# pcb.net
KiCad netlist of a schematic drawn in EAGLE
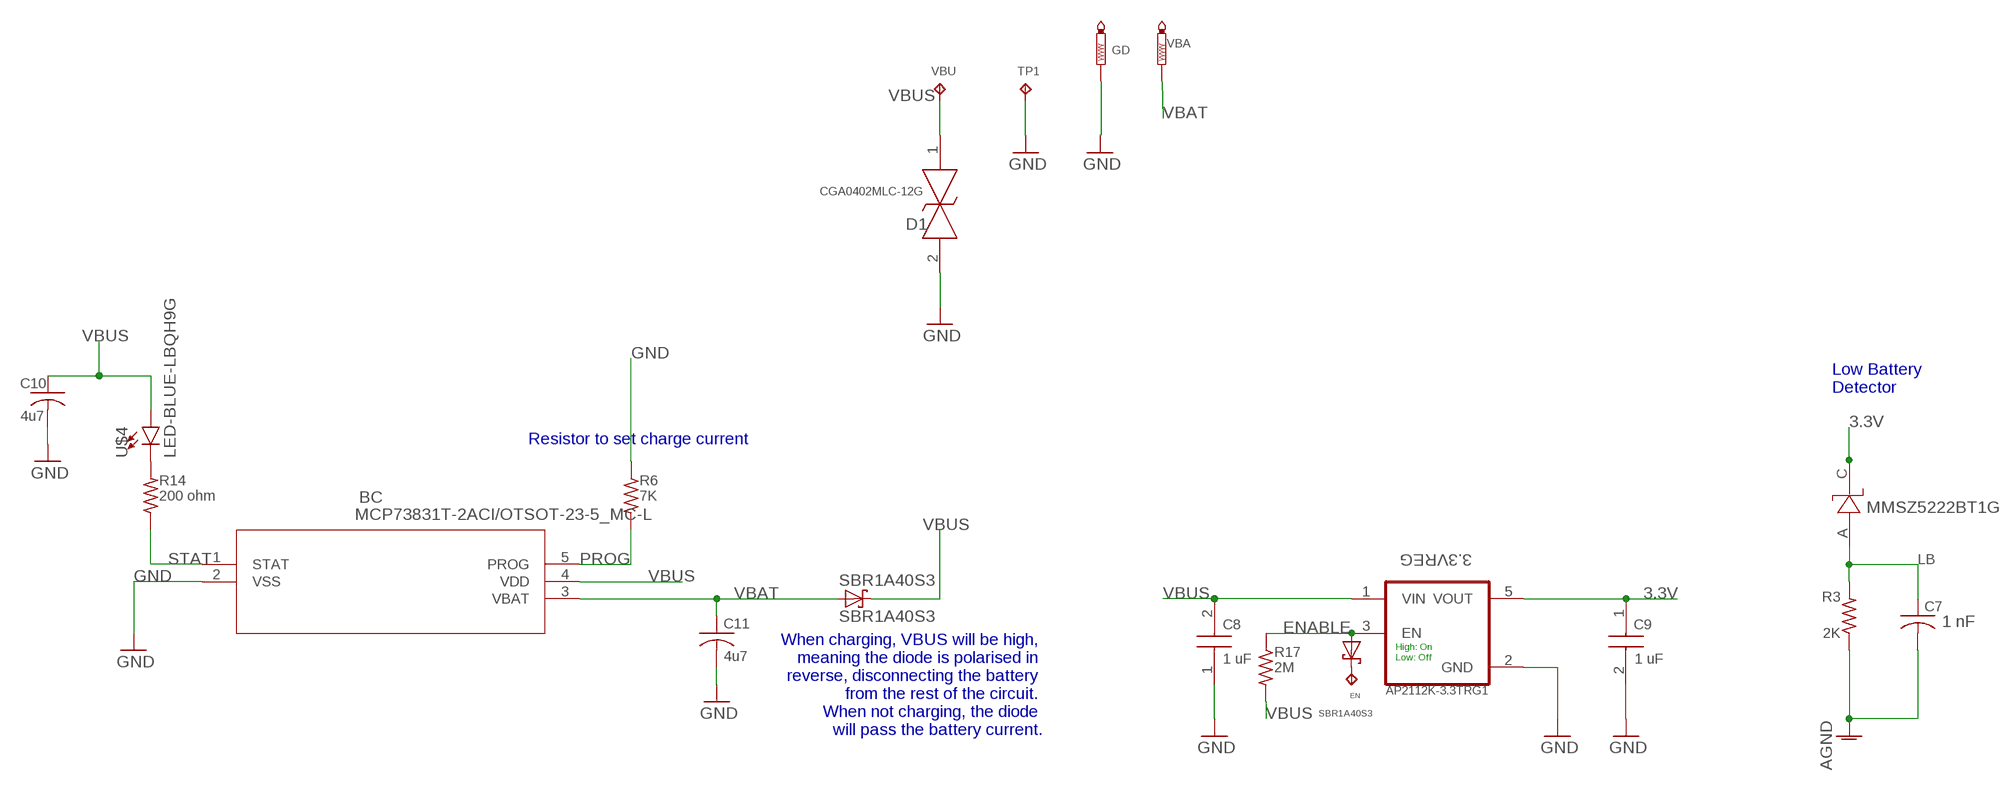
[diagram p0: schematic, sheet 1, part 1 of 2]
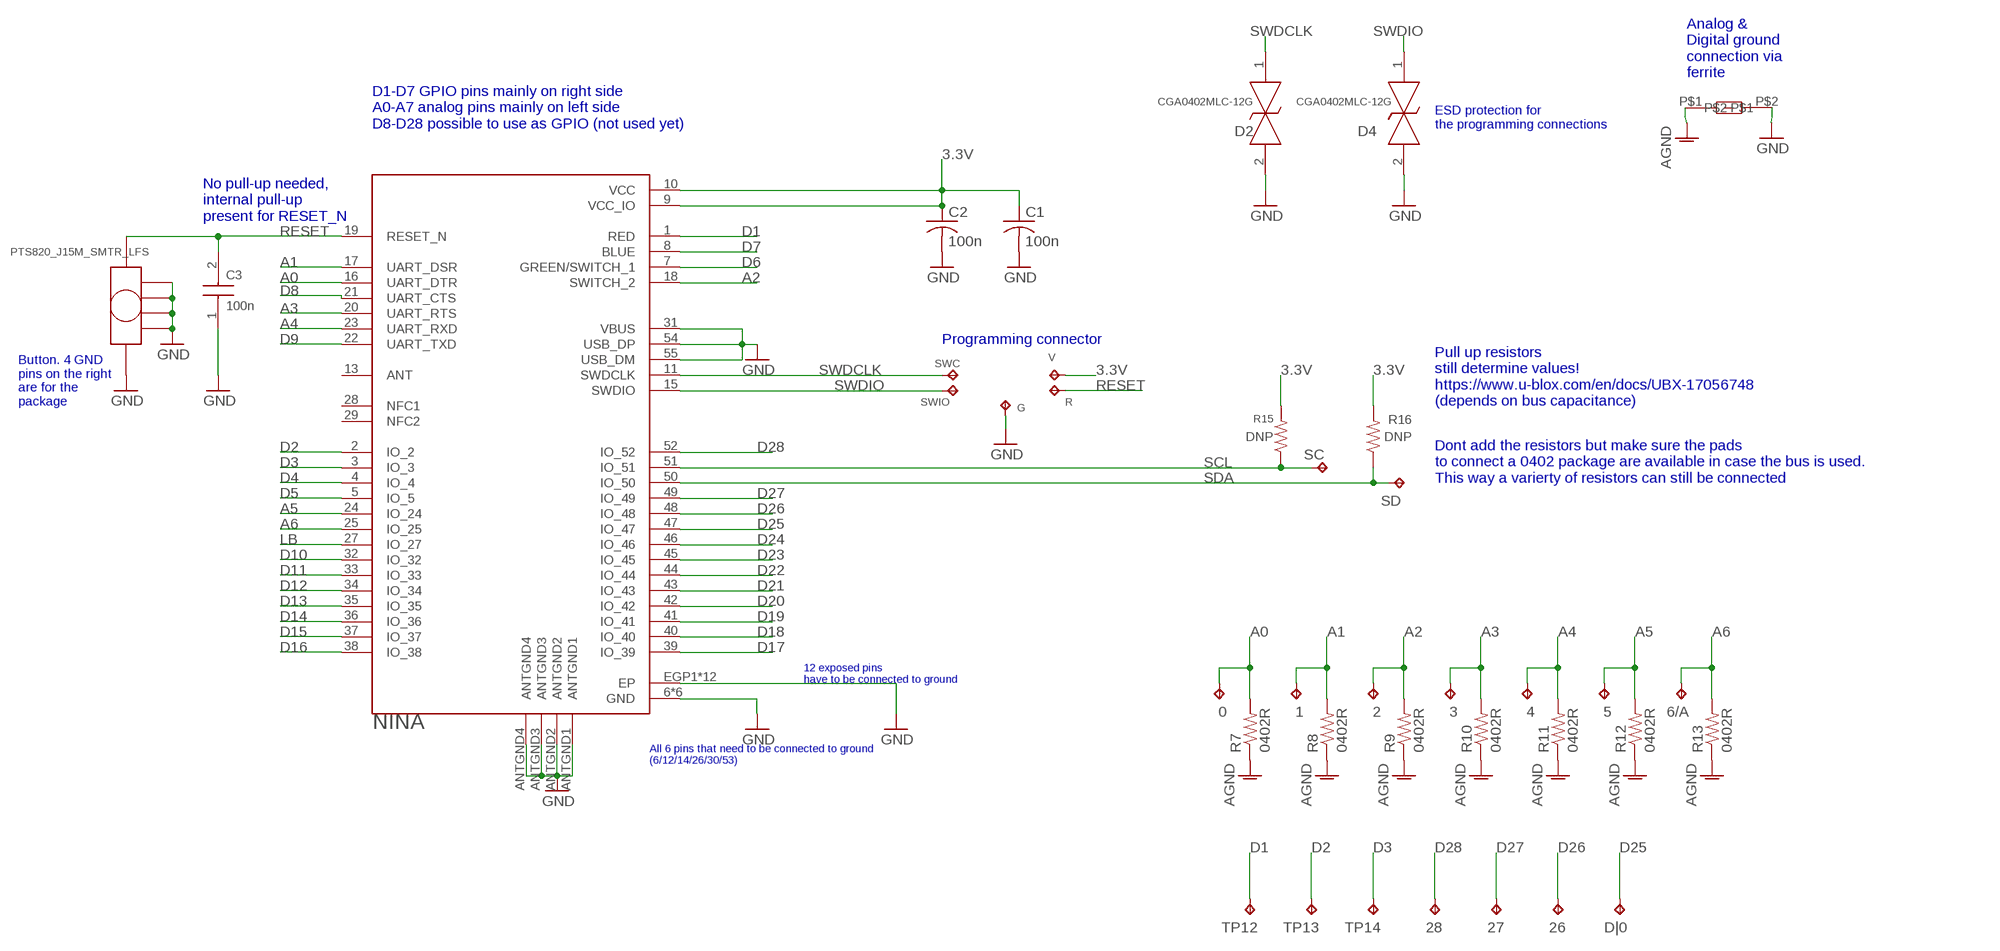
[diagram p1: schematic, sheet 1, part 2 of 2]

(export (version "E")
  (design (tool "Eeschema 10.0.6"))
  (components
    (comp (ref "0")
      (value "CUSTOM_HOLE1")
      (footprint "eagle-import:CUSTOM_HOLE")
      (libsource (lib "eagle-import") (part "CUSTOM_HOLE1"))
    )
    (comp (ref "1")
      (value "CUSTOM_HOLE1")
      (footprint "eagle-import:CUSTOM_HOLE")
      (libsource (lib "eagle-import") (part "CUSTOM_HOLE1"))
    )
    (comp (ref "2")
      (value "CUSTOM_HOLE1")
      (footprint "eagle-import:CUSTOM_HOLE")
      (libsource (lib "eagle-import") (part "CUSTOM_HOLE1"))
    )
    (comp (ref "3")
      (value "CUSTOM_HOLE1")
      (footprint "eagle-import:CUSTOM_HOLE")
      (libsource (lib "eagle-import") (part "CUSTOM_HOLE1"))
    )
    (comp (ref "3.3VREG")
      (value "AP2112K-3.3TRG1")
      (footprint "eagle-import:SOT95P285X140-5N")
      (fields (field (name "MF") "Diodes Inc."))
      (libsource (lib "eagle-import") (part "AP2112K-3.3TRG1"))
    )
    (comp (ref "4")
      (value "CUSTOM_HOLE1")
      (footprint "eagle-import:CUSTOM_HOLE")
      (libsource (lib "eagle-import") (part "CUSTOM_HOLE1"))
    )
    (comp (ref "5")
      (value "CUSTOM_HOLE1")
      (footprint "eagle-import:CUSTOM_HOLE")
      (libsource (lib "eagle-import") (part "CUSTOM_HOLE1"))
    )
    (comp (ref "6/A")
      (value "CUSTOM_HOLE1")
      (footprint "eagle-import:CUSTOM_HOLE")
      (libsource (lib "eagle-import") (part "CUSTOM_HOLE1"))
    )
    (comp (ref "26")
      (value "CUSTOM_HOLE1")
      (footprint "eagle-import:CUSTOM_HOLE")
      (libsource (lib "eagle-import") (part "CUSTOM_HOLE1"))
    )
    (comp (ref "27")
      (value "CUSTOM_HOLE1")
      (footprint "eagle-import:CUSTOM_HOLE")
      (libsource (lib "eagle-import") (part "CUSTOM_HOLE1"))
    )
    (comp (ref "28")
      (value "CUSTOM_HOLE1")
      (footprint "eagle-import:CUSTOM_HOLE")
      (libsource (lib "eagle-import") (part "CUSTOM_HOLE1"))
    )
    (comp (ref "BC")
      (value "MCP73831T-2ACI/OTSOT-23-5_MC-L")
      (footprint "eagle-import:SOT-23-5_MC-L")
      (fields (field (name "MANUFACTURER_PART_NUMBER") "MCP73831T-2ACI/OT"))
      (libsource (lib "eagle-import") (part "MCP73831T-2ACI/OTSOT-23-5_MC-L"))
    )
    (comp (ref "BUTTON")
      (value "PTS820_J15M_SMTR_LFS")
      (footprint "eagle-import:PTS820_J15")
      (fields
        (field (name "MANUFACTURER_PART_NUMBER") "PTS820 J15M SMTR LFS")
        (field (name "MOUSER_PART_NUMBER") "611-PTS820J15MSMTR")
        (field (name "RS_PART_NUMBER") "1359503P")
      )
      (libsource (lib "eagle-import") (part "PTS820_J15M_SMTR_LFS"))
    )
    (comp (ref "C1")
      (value "100n")
      (footprint "eagle-import:C0402")
      (libsource (lib "eagle-import") (part "C-USC0402"))
    )
    (comp (ref "C2")
      (value "100n")
      (footprint "eagle-import:C0402")
      (libsource (lib "eagle-import") (part "C-USC0402"))
    )
    (comp (ref "C3")
      (value "100n")
      (footprint "eagle-import:CAPC1005X33N")
      (fields
        (field (name "MANUFACTURER_PART_NUMBER") "JMK105BJ105KP-F")
        (field (name "MOUSER_PART_NUMBER") "963-JMK105BJ105KP-F")
      )
      (libsource (lib "eagle-import") (part "JMK105BJ105KP-F"))
    )
    (comp (ref "C7")
      (value "1 nF")
      (footprint "eagle-import:C0402")
      (libsource (lib "eagle-import") (part "C-USC0402"))
    )
    (comp (ref "C8")
      (value "1 uF")
      (footprint "eagle-import:CAPC1005X33N")
      (fields
        (field (name "MANUFACTURER_PART_NUMBER") "JMK105BJ105KP-F")
        (field (name "MOUSER_PART_NUMBER") "963-JMK105BJ105KP-F")
      )
      (libsource (lib "eagle-import") (part "JMK105BJ105KP-F"))
    )
    (comp (ref "C9")
      (value "1 uF")
      (footprint "eagle-import:CAPC1005X33N")
      (fields
        (field (name "MANUFACTURER_PART_NUMBER") "JMK105BJ105KP-F")
        (field (name "MOUSER_PART_NUMBER") "963-JMK105BJ105KP-F")
      )
      (libsource (lib "eagle-import") (part "JMK105BJ105KP-F"))
    )
    (comp (ref "C10")
      (value "4u7")
      (footprint "eagle-import:C0402")
      (libsource (lib "eagle-import") (part "C-USC0402"))
    )
    (comp (ref "C11")
      (value "4u7")
      (footprint "eagle-import:C0402")
      (libsource (lib "eagle-import") (part "C-USC0402"))
    )
    (comp (ref "D1")
      (value "CGA0402MLC-12G")
      (footprint "eagle-import:CGA0402MLC12G")
      (fields (field (name "MOUSER_PART_NUMBER") "652-CGA0402MLC-12G"))
      (libsource (lib "eagle-import") (part "CGA0402MLC-12G"))
    )
    (comp (ref "D2")
      (value "CGA0402MLC-12G")
      (footprint "eagle-import:CGA0402MLC12G")
      (fields (field (name "MOUSER_PART_NUMBER") "652-CGA0402MLC-12G"))
      (libsource (lib "eagle-import") (part "CGA0402MLC-12G"))
    )
    (comp (ref "D4")
      (value "CGA0402MLC-12G")
      (footprint "eagle-import:CGA0402MLC12G")
      (fields (field (name "MOUSER_PART_NUMBER") "652-CGA0402MLC-12G"))
      (libsource (lib "eagle-import") (part "CGA0402MLC-12G"))
    )
    (comp (ref "D|0")
      (value "CUSTOM_HOLE1")
      (footprint "eagle-import:CUSTOM_HOLE")
      (libsource (lib "eagle-import") (part "CUSTOM_HOLE1"))
    )
    (comp (ref "EN")
      (value "CUSTOM_HOLE1")
      (footprint "eagle-import:CUSTOM_HOLE")
      (libsource (lib "eagle-import") (part "CUSTOM_HOLE1"))
    )
    (comp (ref "G")
      (value "TPB1,27")
      (footprint "eagle-import:B1,27")
      (libsource (lib "eagle-import") (part "TPB1,27"))
    )
    (comp (ref "GD")
      (value "PTR1TP18R")
      (footprint "eagle-import:TP18R")
      (libsource (lib "eagle-import") (part "PTR1TP18R"))
    )
    (comp (ref "MMSZ5222BT1G")
      (value "MMSZ5222BT1G")
      (footprint "eagle-import:SOD−123")
      (libsource (lib "eagle-import") (part "MMSZ5222BT1G"))
    )
    (comp (ref "R")
      (value "TPB1,27")
      (footprint "eagle-import:B1,27")
      (libsource (lib "eagle-import") (part "TPB1,27"))
    )
    (comp (ref "R3")
      (value "2K")
      (footprint "eagle-import:RESC1005X40N")
      (libsource (lib "eagle-import") (part "0402R"))
    )
    (comp (ref "R6")
      (value "7K")
      (footprint "eagle-import:RESC1005X40N")
      (libsource (lib "eagle-import") (part "0402R"))
    )
    (comp (ref "R7")
      (value "0402R")
      (footprint "eagle-import:RESC1005X40N")
      (libsource (lib "eagle-import") (part "0402R"))
    )
    (comp (ref "R8")
      (value "0402R")
      (footprint "eagle-import:RESC1005X40N")
      (libsource (lib "eagle-import") (part "0402R"))
    )
    (comp (ref "R9")
      (value "0402R")
      (footprint "eagle-import:RESC1005X40N")
      (libsource (lib "eagle-import") (part "0402R"))
    )
    (comp (ref "R10")
      (value "0402R")
      (footprint "eagle-import:RESC1005X40N")
      (libsource (lib "eagle-import") (part "0402R"))
    )
    (comp (ref "R11")
      (value "0402R")
      (footprint "eagle-import:RESC1005X40N")
      (libsource (lib "eagle-import") (part "0402R"))
    )
    (comp (ref "R12")
      (value "0402R")
      (footprint "eagle-import:RESC1005X40N")
      (libsource (lib "eagle-import") (part "0402R"))
    )
    (comp (ref "R13")
      (value "0402R")
      (footprint "eagle-import:RESC1005X40N")
      (libsource (lib "eagle-import") (part "0402R"))
    )
    (comp (ref "R14")
      (value "200 ohm")
      (footprint "eagle-import:RESC1005X40N")
      (libsource (lib "eagle-import") (part "0402R"))
    )
    (comp (ref "R15")
      (value "DNP")
      (footprint "eagle-import:RESC1005X40N")
      (libsource (lib "eagle-import") (part "0402R"))
    )
    (comp (ref "R16")
      (value "DNP")
      (footprint "eagle-import:RESC1005X40N")
      (libsource (lib "eagle-import") (part "0402R"))
    )
    (comp (ref "R17")
      (value "2M")
      (footprint "eagle-import:RESC1005X40N")
      (libsource (lib "eagle-import") (part "0402R"))
    )
    (comp (ref "SBR1A40S3")
      (value "SBR1A40S3")
      (footprint "eagle-import:SOD323")
      (libsource (lib "eagle-import") (part "SBR1A40S3"))
    )
    (comp (ref "SC")
      (value "CUSTOM_HOLE1")
      (footprint "eagle-import:CUSTOM_HOLE")
      (libsource (lib "eagle-import") (part "CUSTOM_HOLE1"))
    )
    (comp (ref "SD")
      (value "CUSTOM_HOLE1")
      (footprint "eagle-import:CUSTOM_HOLE")
      (libsource (lib "eagle-import") (part "CUSTOM_HOLE1"))
    )
    (comp (ref "SWC")
      (value "TPB1,27")
      (footprint "eagle-import:B1,27")
      (libsource (lib "eagle-import") (part "TPB1,27"))
    )
    (comp (ref "SWIO")
      (value "TPB1,27")
      (footprint "eagle-import:B1,27")
      (libsource (lib "eagle-import") (part "TPB1,27"))
    )
    (comp (ref "TP1")
      (value "CUSTOM_HOLE1")
      (footprint "eagle-import:CUSTOM_HOLE")
      (libsource (lib "eagle-import") (part "CUSTOM_HOLE1"))
    )
    (comp (ref "TP12")
      (value "CUSTOM_HOLE1")
      (footprint "eagle-import:CUSTOM_HOLE")
      (libsource (lib "eagle-import") (part "CUSTOM_HOLE1"))
    )
    (comp (ref "TP13")
      (value "CUSTOM_HOLE1")
      (footprint "eagle-import:CUSTOM_HOLE")
      (libsource (lib "eagle-import") (part "CUSTOM_HOLE1"))
    )
    (comp (ref "TP14")
      (value "CUSTOM_HOLE1")
      (footprint "eagle-import:CUSTOM_HOLE")
      (libsource (lib "eagle-import") (part "CUSTOM_HOLE1"))
    )
    (comp (ref "U$2")
      (value "SBR1A40S3")
      (footprint "eagle-import:SOD323")
      (libsource (lib "eagle-import") (part "SBR1A40S3"))
    )
    (comp (ref "U$4")
      (value "LED-BLUE-LBQH9G")
      (footprint "eagle-import:LBQH9G-0402")
      (libsource (lib "eagle-import") (part "LED-BLUE-LBQH9G"))
    )
    (comp (ref "U$5")
      (value "BLM18KG121WH1D")
      (footprint "eagle-import:0603")
      (libsource (lib "eagle-import") (part "BLM18KG121WH1D"))
    )
    (comp (ref "U1")
      (value "NINA")
      (footprint "eagle-import:XCVR_NINA-B306")
      (fields (field (name "MF") "U-Blox America Inc.") (field (name "MP") "NINA-B311-00B"))
      (libsource (lib "eagle-import") (part "NINA-B306"))
    )
    (comp (ref "V")
      (value "TPB1,27")
      (footprint "eagle-import:B1,27")
      (libsource (lib "eagle-import") (part "TPB1,27"))
    )
    (comp (ref "VBA")
      (value "PTR1TP18R")
      (footprint "eagle-import:TP18R")
      (libsource (lib "eagle-import") (part "PTR1TP18R"))
    )
    (comp (ref "VBU")
      (value "CUSTOM_HOLE1")
      (footprint "eagle-import:CUSTOM_HOLE")
      (libsource (lib "eagle-import") (part "CUSTOM_HOLE1"))
    )
  )
  (nets
    (net (code "1") (name "/3.3V") (class "Default")
      (node (ref "3.3VREG") (pin "5") (pinfunction "VOUT_5") (pintype "power_in"))
      (node (ref "C1") (pin "1") (pinfunction "1_1") (pintype "passive"))
      (node (ref "C2") (pin "1") (pinfunction "1_1") (pintype "passive"))
      (node (ref "C9") (pin "1") (pinfunction "1_1") (pintype "bidirectional"))
      (node (ref "MMSZ5222BT1G") (pin "C") (pinfunction "C_C") (pintype "bidirectional"))
      (node (ref "R15") (pin "2") (pinfunction "2_2") (pintype "passive"))
      (node (ref "R16") (pin "2") (pinfunction "2_2") (pintype "passive"))
      (node (ref "U1") (pin "10") (pinfunction "VCC_10") (pintype "power_in"))
      (node (ref "U1") (pin "9") (pinfunction "VCC_IO_9") (pintype "power_in"))
      (node (ref "V") (pin "TP") (pinfunction "TP_TP") (pintype "input"))
    )
    (net (code "2") (name "/A0") (class "Default")
      (node (ref "0") (pin "P$1") (pinfunction "TP_P$1") (pintype "input"))
      (node (ref "R7") (pin "2") (pinfunction "2_2") (pintype "passive"))
      (node (ref "U1") (pin "16") (pinfunction "UART_DTR_16") (pintype "output"))
    )
    (net (code "3") (name "/A1") (class "Default")
      (node (ref "1") (pin "P$1") (pinfunction "TP_P$1") (pintype "input"))
      (node (ref "R8") (pin "2") (pinfunction "2_2") (pintype "passive"))
      (node (ref "U1") (pin "17") (pinfunction "UART_DSR_17") (pintype "input"))
    )
    (net (code "4") (name "/A2") (class "Default")
      (node (ref "2") (pin "P$1") (pinfunction "TP_P$1") (pintype "input"))
      (node (ref "R9") (pin "2") (pinfunction "2_2") (pintype "passive"))
      (node (ref "U1") (pin "18") (pinfunction "SWITCH_2_18") (pintype "input"))
    )
    (net (code "5") (name "/A3") (class "Default")
      (node (ref "3") (pin "P$1") (pinfunction "TP_P$1") (pintype "input"))
      (node (ref "R10") (pin "2") (pinfunction "2_2") (pintype "passive"))
      (node (ref "U1") (pin "20") (pinfunction "UART_RTS_20") (pintype "output"))
    )
    (net (code "6") (name "/A4") (class "Default")
      (node (ref "4") (pin "P$1") (pinfunction "TP_P$1") (pintype "input"))
      (node (ref "R11") (pin "2") (pinfunction "2_2") (pintype "passive"))
      (node (ref "U1") (pin "23") (pinfunction "UART_RXD_23") (pintype "input"))
    )
    (net (code "7") (name "/A5") (class "Default")
      (node (ref "5") (pin "P$1") (pinfunction "TP_P$1") (pintype "input"))
      (node (ref "R12") (pin "2") (pinfunction "2_2") (pintype "passive"))
      (node (ref "U1") (pin "24") (pinfunction "IO_24_24") (pintype "bidirectional"))
    )
    (net (code "8") (name "/A6") (class "Default")
      (node (ref "6/A") (pin "P$1") (pinfunction "TP_P$1") (pintype "input"))
      (node (ref "R13") (pin "2") (pinfunction "2_2") (pintype "passive"))
      (node (ref "U1") (pin "25") (pinfunction "IO_25_25") (pintype "bidirectional"))
    )
    (net (code "9") (name "/D1") (class "Default")
      (node (ref "TP12") (pin "P$1") (pinfunction "TP_P$1") (pintype "input"))
      (node (ref "U1") (pin "1") (pinfunction "RED_1") (pintype "output"))
    )
    (net (code "10") (name "/D2") (class "Default")
      (node (ref "TP13") (pin "P$1") (pinfunction "TP_P$1") (pintype "input"))
      (node (ref "U1") (pin "2") (pinfunction "IO_2_2") (pintype "bidirectional"))
    )
    (net (code "11") (name "/D3") (class "Default")
      (node (ref "TP14") (pin "P$1") (pinfunction "TP_P$1") (pintype "input"))
      (node (ref "U1") (pin "3") (pinfunction "IO_3_3") (pintype "bidirectional"))
    )
    (net (code "12") (name "/D4") (class "Default")
      (node (ref "U1") (pin "4") (pinfunction "IO_4_4") (pintype "bidirectional"))
    )
    (net (code "13") (name "/D5") (class "Default")
      (node (ref "U1") (pin "5") (pinfunction "IO_5_5") (pintype "bidirectional"))
    )
    (net (code "14") (name "/D6") (class "Default")
      (node (ref "U1") (pin "7") (pinfunction "GREEN/SWITCH_1_7") (pintype "bidirectional"))
    )
    (net (code "15") (name "/D7") (class "Default")
      (node (ref "U1") (pin "8") (pinfunction "BLUE_8") (pintype "output"))
    )
    (net (code "16") (name "/D8") (class "Default")
      (node (ref "U1") (pin "21") (pinfunction "UART_CTS_21") (pintype "input"))
    )
    (net (code "17") (name "/D9") (class "Default")
      (node (ref "U1") (pin "22") (pinfunction "UART_TXD_22") (pintype "output"))
    )
    (net (code "18") (name "/D10") (class "Default")
      (node (ref "U1") (pin "32") (pinfunction "IO_32_32") (pintype "bidirectional"))
    )
    (net (code "19") (name "/D11") (class "Default")
      (node (ref "U1") (pin "33") (pinfunction "IO_33_33") (pintype "bidirectional"))
    )
    (net (code "20") (name "/D12") (class "Default")
      (node (ref "U1") (pin "34") (pinfunction "IO_34_34") (pintype "bidirectional"))
    )
    (net (code "21") (name "/D13") (class "Default")
      (node (ref "U1") (pin "35") (pinfunction "IO_35_35") (pintype "bidirectional"))
    )
    (net (code "22") (name "/D14") (class "Default")
      (node (ref "U1") (pin "36") (pinfunction "IO_36_36") (pintype "bidirectional"))
    )
    (net (code "23") (name "/D15") (class "Default")
      (node (ref "U1") (pin "37") (pinfunction "IO_37_37") (pintype "bidirectional"))
    )
    (net (code "24") (name "/D16") (class "Default")
      (node (ref "U1") (pin "38") (pinfunction "IO_38_38") (pintype "bidirectional"))
    )
    (net (code "25") (name "/D17") (class "Default")
      (node (ref "U1") (pin "39") (pinfunction "IO_39_39") (pintype "bidirectional"))
    )
    (net (code "26") (name "/D18") (class "Default")
      (node (ref "U1") (pin "40") (pinfunction "IO_40_40") (pintype "bidirectional"))
    )
    (net (code "27") (name "/D19") (class "Default")
      (node (ref "U1") (pin "41") (pinfunction "IO_41_41") (pintype "bidirectional"))
    )
    (net (code "28") (name "/D20") (class "Default")
      (node (ref "U1") (pin "42") (pinfunction "IO_42_42") (pintype "bidirectional"))
    )
    (net (code "29") (name "/D21") (class "Default")
      (node (ref "U1") (pin "43") (pinfunction "IO_43_43") (pintype "bidirectional"))
    )
    (net (code "30") (name "/D22") (class "Default")
      (node (ref "U1") (pin "44") (pinfunction "IO_44_44") (pintype "bidirectional"))
    )
    (net (code "31") (name "/D23") (class "Default")
      (node (ref "U1") (pin "45") (pinfunction "IO_45_45") (pintype "bidirectional"))
    )
    (net (code "32") (name "/D24") (class "Default")
      (node (ref "U1") (pin "46") (pinfunction "IO_46_46") (pintype "bidirectional"))
    )
    (net (code "33") (name "/D25") (class "Default")
      (node (ref "D|0") (pin "P$1") (pinfunction "TP_P$1") (pintype "input"))
      (node (ref "U1") (pin "47") (pinfunction "IO_47_47") (pintype "bidirectional"))
    )
    (net (code "34") (name "/D26") (class "Default")
      (node (ref "26") (pin "P$1") (pinfunction "TP_P$1") (pintype "input"))
      (node (ref "U1") (pin "48") (pinfunction "IO_48_48") (pintype "bidirectional"))
    )
    (net (code "35") (name "/D27") (class "Default")
      (node (ref "27") (pin "P$1") (pinfunction "TP_P$1") (pintype "input"))
      (node (ref "U1") (pin "49") (pinfunction "IO_49_49") (pintype "bidirectional"))
    )
    (net (code "36") (name "/D28") (class "Default")
      (node (ref "28") (pin "P$1") (pinfunction "TP_P$1") (pintype "input"))
      (node (ref "U1") (pin "52") (pinfunction "IO_52_52") (pintype "bidirectional"))
    )
    (net (code "37") (name "/ENABLE") (class "Default")
      (node (ref "3.3VREG") (pin "3") (pinfunction "EN_3") (pintype "input"))
      (node (ref "R17") (pin "1") (pinfunction "1_1") (pintype "passive"))
      (node (ref "U$2") (pin "A") (pinfunction "A_A") (pintype "passive"))
    )
    (net (code "38") (name "/LB") (class "Default")
      (node (ref "C7") (pin "1") (pinfunction "1_1") (pintype "passive"))
      (node (ref "MMSZ5222BT1G") (pin "A") (pinfunction "A_A") (pintype "bidirectional"))
      (node (ref "R3") (pin "2") (pinfunction "2_2") (pintype "passive"))
      (node (ref "U1") (pin "27") (pinfunction "IO_27_27") (pintype "bidirectional"))
    )
    (net (code "39") (name "/PROG") (class "Default")
      (node (ref "BC") (pin "5") (pinfunction "PROG_5") (pintype "passive"))
      (node (ref "R6") (pin "2") (pinfunction "2_2") (pintype "passive"))
    )
    (net (code "40") (name "/RESET") (class "Default")
      (node (ref "BUTTON") (pin "2") (pinfunction "2_2") (pintype "bidirectional"))
      (node (ref "C3") (pin "2") (pinfunction "2_2") (pintype "bidirectional"))
      (node (ref "R") (pin "TP") (pinfunction "TP_TP") (pintype "input"))
      (node (ref "U1") (pin "19") (pinfunction "RESET_N_19") (pintype "input"))
    )
    (net (code "41") (name "/SCL") (class "Default")
      (node (ref "R15") (pin "1") (pinfunction "1_1") (pintype "passive"))
      (node (ref "SC") (pin "P$1") (pinfunction "TP_P$1") (pintype "input"))
      (node (ref "U1") (pin "51") (pinfunction "IO_51_51") (pintype "bidirectional"))
    )
    (net (code "42") (name "/SDA") (class "Default")
      (node (ref "R16") (pin "1") (pinfunction "1_1") (pintype "passive"))
      (node (ref "SD") (pin "P$1") (pinfunction "TP_P$1") (pintype "input"))
      (node (ref "U1") (pin "50") (pinfunction "IO_50_50") (pintype "bidirectional"))
    )
    (net (code "43") (name "/STAT") (class "Default")
      (node (ref "BC") (pin "1") (pinfunction "STAT_1") (pintype "passive"))
      (node (ref "R14") (pin "1") (pinfunction "1_1") (pintype "passive"))
    )
    (net (code "44") (name "/SWDCLK") (class "Default")
      (node (ref "D2") (pin "1") (pinfunction "1_1") (pintype "bidirectional"))
      (node (ref "SWC") (pin "TP") (pinfunction "TP_TP") (pintype "input"))
      (node (ref "U1") (pin "11") (pinfunction "SWDCLK_11") (pintype "bidirectional"))
    )
    (net (code "45") (name "/SWDIO") (class "Default")
      (node (ref "D4") (pin "1") (pinfunction "1_1") (pintype "bidirectional"))
      (node (ref "SWIO") (pin "TP") (pinfunction "TP_TP") (pintype "input"))
      (node (ref "U1") (pin "15") (pinfunction "SWDIO_15") (pintype "bidirectional"))
    )
    (net (code "46") (name "/VBAT") (class "Default")
      (node (ref "BC") (pin "3") (pinfunction "VBAT_3") (pintype "passive"))
      (node (ref "C11") (pin "1") (pinfunction "1_1") (pintype "passive"))
      (node (ref "SBR1A40S3") (pin "A") (pinfunction "A_A") (pintype "passive"))
      (node (ref "VBA") (pin "TP") (pinfunction "TP_TP") (pintype "input"))
    )
    (net (code "47") (name "/VBUS") (class "Default")
      (node (ref "3.3VREG") (pin "1") (pinfunction "VIN_1") (pintype "power_in"))
      (node (ref "BC") (pin "4") (pinfunction "VDD_4") (pintype "passive"))
      (node (ref "C10") (pin "1") (pinfunction "1_1") (pintype "passive"))
      (node (ref "C8") (pin "2") (pinfunction "2_2") (pintype "bidirectional"))
      (node (ref "D1") (pin "1") (pinfunction "1_1") (pintype "bidirectional"))
      (node (ref "R17") (pin "2") (pinfunction "2_2") (pintype "passive"))
      (node (ref "SBR1A40S3") (pin "C") (pinfunction "C_C") (pintype "passive"))
      (node (ref "U$4") (pin "A") (pinfunction "A_A") (pintype "passive"))
      (node (ref "VBU") (pin "P$1") (pinfunction "TP_P$1") (pintype "input"))
    )
    (net (code "48") (name "AGND") (class "Default")
      (node (ref "C7") (pin "2") (pinfunction "2_2") (pintype "passive"))
      (node (ref "R10") (pin "1") (pinfunction "1_1") (pintype "passive"))
      (node (ref "R11") (pin "1") (pinfunction "1_1") (pintype "passive"))
      (node (ref "R12") (pin "1") (pinfunction "1_1") (pintype "passive"))
      (node (ref "R13") (pin "1") (pinfunction "1_1") (pintype "passive"))
      (node (ref "R3") (pin "1") (pinfunction "1_1") (pintype "passive"))
      (node (ref "R7") (pin "1") (pinfunction "1_1") (pintype "passive"))
      (node (ref "R8") (pin "1") (pinfunction "1_1") (pintype "passive"))
      (node (ref "R9") (pin "1") (pinfunction "1_1") (pintype "passive"))
      (node (ref "U$5") (pin "P$1") (pinfunction "P$1_P$1") (pintype "bidirectional"))
    )
    (net (code "49") (name "GND") (class "Default")
      (node (ref "3.3VREG") (pin "2") (pinfunction "GND_2") (pintype "power_in"))
      (node (ref "BC") (pin "2") (pinfunction "VSS_2") (pintype "passive"))
      (node (ref "BUTTON") (pin "1") (pinfunction "1_1") (pintype "bidirectional"))
      (node (ref "BUTTON") (pin "P$1") (pinfunction "P$1_P$1") (pintype "bidirectional"))
      (node (ref "BUTTON") (pin "P$2") (pinfunction "P$2_P$2") (pintype "bidirectional"))
      (node (ref "BUTTON") (pin "P$3") (pinfunction "P$3_P$3") (pintype "bidirectional"))
      (node (ref "BUTTON") (pin "P$4") (pinfunction "P$4_P$4") (pintype "bidirectional"))
      (node (ref "C1") (pin "2") (pinfunction "2_2") (pintype "passive"))
      (node (ref "C10") (pin "2") (pinfunction "2_2") (pintype "passive"))
      (node (ref "C11") (pin "2") (pinfunction "2_2") (pintype "passive"))
      (node (ref "C2") (pin "2") (pinfunction "2_2") (pintype "passive"))
      (node (ref "C3") (pin "1") (pinfunction "1_1") (pintype "bidirectional"))
      (node (ref "C8") (pin "1") (pinfunction "1_1") (pintype "bidirectional"))
      (node (ref "C9") (pin "2") (pinfunction "2_2") (pintype "bidirectional"))
      (node (ref "D1") (pin "2") (pinfunction "2_2") (pintype "bidirectional"))
      (node (ref "D2") (pin "2") (pinfunction "2_2") (pintype "bidirectional"))
      (node (ref "D4") (pin "2") (pinfunction "2_2") (pintype "bidirectional"))
      (node (ref "G") (pin "TP") (pinfunction "TP_TP") (pintype "input"))
      (node (ref "GD") (pin "TP") (pinfunction "TP_TP") (pintype "input"))
      (node (ref "R6") (pin "1") (pinfunction "1_1") (pintype "passive"))
      (node (ref "TP1") (pin "P$1") (pinfunction "TP_P$1") (pintype "input"))
      (node (ref "U$5") (pin "P$2") (pinfunction "P$2_P$2") (pintype "bidirectional"))
      (node (ref "U1") (pin "12") (pinfunction "GND_12") (pintype "power_in"))
      (node (ref "U1") (pin "14") (pinfunction "GND_14") (pintype "power_in"))
      (node (ref "U1") (pin "26") (pinfunction "GND_26") (pintype "power_in"))
      (node (ref "U1") (pin "30") (pinfunction "GND_30") (pintype "power_in"))
      (node (ref "U1") (pin "31") (pinfunction "VBUS_31") (pintype "bidirectional"))
      (node (ref "U1") (pin "53") (pinfunction "GND_53") (pintype "power_in"))
      (node (ref "U1") (pin "54") (pinfunction "USB_DP_54") (pintype "bidirectional"))
      (node (ref "U1") (pin "55") (pinfunction "USB_DM_55") (pintype "bidirectional"))
      (node (ref "U1") (pin "6") (pinfunction "GND_6") (pintype "power_in"))
      (node (ref "U1") (pin "ANTGND1") (pinfunction "ANTGND1_ANTGND1") (pintype "bidirectional"))
      (node (ref "U1") (pin "ANTGND2") (pinfunction "ANTGND2_ANTGND2") (pintype "bidirectional"))
      (node (ref "U1") (pin "ANTGND3") (pinfunction "ANTGND3_ANTGND3") (pintype "bidirectional"))
      (node (ref "U1") (pin "ANTGND4") (pinfunction "ANTGND4_ANTGND4") (pintype "bidirectional"))
      (node (ref "U1") (pin "EGP1") (pinfunction "EP_EGP1") (pintype "power_in"))
      (node (ref "U1") (pin "EGP10") (pinfunction "EP_EGP10") (pintype "power_in"))
      (node (ref "U1") (pin "EGP11") (pinfunction "EP_EGP11") (pintype "power_in"))
      (node (ref "U1") (pin "EGP12") (pinfunction "EP_EGP12") (pintype "power_in"))
      (node (ref "U1") (pin "EGP2") (pinfunction "EP_EGP2") (pintype "power_in"))
      (node (ref "U1") (pin "EGP3") (pinfunction "EP_EGP3") (pintype "power_in"))
      (node (ref "U1") (pin "EGP4") (pinfunction "EP_EGP4") (pintype "power_in"))
      (node (ref "U1") (pin "EGP5") (pinfunction "EP_EGP5") (pintype "power_in"))
      (node (ref "U1") (pin "EGP6") (pinfunction "EP_EGP6") (pintype "power_in"))
      (node (ref "U1") (pin "EGP7") (pinfunction "EP_EGP7") (pintype "power_in"))
      (node (ref "U1") (pin "EGP8") (pinfunction "EP_EGP8") (pintype "power_in"))
      (node (ref "U1") (pin "EGP9") (pinfunction "EP_EGP9") (pintype "power_in"))
    )
    (net (code "50") (name "Net-(EN-TP)") (class "Default")
      (node (ref "EN") (pin "P$1") (pinfunction "TP_P$1") (pintype "input"))
      (node (ref "U$2") (pin "C") (pinfunction "C_C") (pintype "passive"))
    )
    (net (code "51") (name "Net-(R14-Pad2)") (class "Default")
      (node (ref "R14") (pin "2") (pinfunction "2_2") (pintype "passive"))
      (node (ref "U$4") (pin "C") (pinfunction "C_C") (pintype "passive"))
    )
    (net (code "52") (name "unconnected-(U1-ANT-Pad13)") (class "Default")
      (node (ref "U1") (pin "13") (pinfunction "ANT_13") (pintype "bidirectional"))
    )
    (net (code "53") (name "unconnected-(U1-NFC1-Pad28)") (class "Default")
      (node (ref "U1") (pin "28") (pinfunction "NFC1_28") (pintype "bidirectional"))
    )
    (net (code "54") (name "unconnected-(U1-NFC2-Pad29)") (class "Default")
      (node (ref "U1") (pin "29") (pinfunction "NFC2_29") (pintype "bidirectional"))
    )
  )
)
